# usb_cuter.net
KiCad netlist of a schematic drawn in Altium Designer
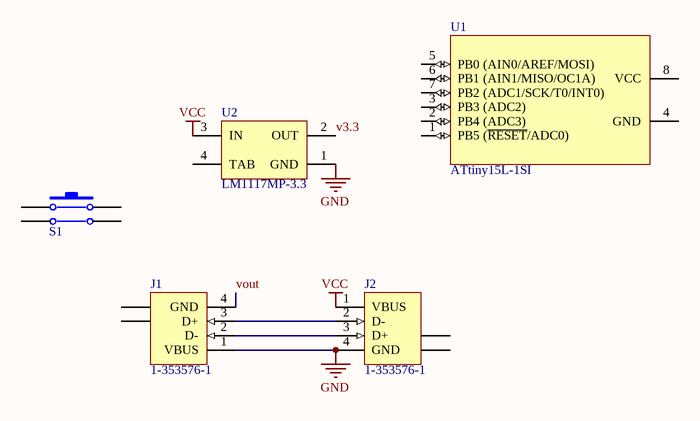
[diagram p0: usb cuter.SchDoc]

(export (version "E")
  (design (tool "Eeschema 10.0.6"))
  (components
    (comp (ref "J1")
      (value "1-353576-1")
      (footprint "353576")
      (description "USB 1.1, Right Angle, SMT, A Type, Receptacle, 4 Position, White")
      (fields (field (name "PUBLISHER") "Altium Limited"))
      (libsource (lib "") (part "1-353576-1_1"))
    )
    (comp (ref "J2")
      (value "1-353576-1")
      (footprint "353576")
      (description "USB 1.1, Right Angle, SMT, A Type, Receptacle, 4 Position, White")
      (fields (field (name "PUBLISHER") "Altium Limited"))
      (libsource (lib "AMP Serial Bus USB") (part "1-353576-1"))
    )
    (comp (ref "S1")
      (value "PUSH BUTTON DOUBLE")
      (footprint "PUSH BUTTON")
      (description "Switch")
      (libsource (lib "AltiumLib1") (part "PUSH BUTTON DOUBLE"))
    )
    (comp (ref "U1")
      (value "ATtiny15L-1SI")
      (footprint "8S2_N")
      (description "8-Bit AVR Microcontroller with 1K Byte of Flash Memory")
      (fields (field (name "PUBLISHER") "Altium Limited"))
      (libsource (lib "Atmel Microcontroller 8-Bit AVR") (part "ATtiny15L-1SI"))
    )
    (comp (ref "U2")
      (value "LM1117MP-3.3")
      (footprint "MP04A_N")
      (description "800mA Low-Dropout Linear Regulator")
      (fields
        (field (name "MANUFACTURER") "National Semiconductor")
        (field (name "DIGIKEYPARTNUMBER") "LM1117MP-3.3CT-ND")
        (field (name "PUBLISHER") "Altium Limited")
      )
      (libsource (lib "NSC LDO") (part "LM1117MP-3.3"))
    )
  )
  (nets
    (net (code "1") (name "/v3.3") (class "Default")
      (node (ref "U2") (pin "2") (pinfunction "OUT_2") (pintype "power_in"))
    )
    (net (code "2") (name "/vout") (class "Default")
      (node (ref "J1") (pin "4") (pinfunction "GND_4") (pintype "power_in"))
    )
    (net (code "3") (name "GND") (class "Default")
      (node (ref "J1") (pin "1") (pinfunction "VBUS_1") (pintype "power_in"))
      (node (ref "J2") (pin "4") (pinfunction "GND_4") (pintype "power_in"))
      (node (ref "U2") (pin "1") (pinfunction "GND_1") (pintype "power_in"))
    )
    (net (code "4") (name "Net-(J1-D+)") (class "Default")
      (node (ref "J1") (pin "3") (pinfunction "D+_3") (pintype "input"))
      (node (ref "J2") (pin "2") (pinfunction "D-_2") (pintype "input"))
    )
    (net (code "5") (name "Net-(J1-D-)") (class "Default")
      (node (ref "J1") (pin "2") (pinfunction "D-_2") (pintype "input"))
      (node (ref "J2") (pin "3") (pinfunction "D+_3") (pintype "input"))
    )
    (net (code "6") (name "VCC") (class "Default")
      (node (ref "J2") (pin "1") (pinfunction "VBUS_1") (pintype "power_in"))
      (node (ref "U2") (pin "3") (pinfunction "IN_3") (pintype "power_in"))
    )
    (net (code "7") (name "unconnected-(J1-SHLD-Pad5)") (class "Default")
      (node (ref "J1") (pin "5") (pinfunction "SHLD_5") (pintype "passive"))
    )
    (net (code "8") (name "unconnected-(J1-SHLD-Pad6)") (class "Default")
      (node (ref "J1") (pin "6") (pinfunction "SHLD_6") (pintype "passive"))
    )
    (net (code "9") (name "unconnected-(J2-SHLD-Pad5)") (class "Default")
      (node (ref "J2") (pin "5") (pinfunction "SHLD_5") (pintype "passive"))
    )
    (net (code "10") (name "unconnected-(J2-SHLD-Pad6)") (class "Default")
      (node (ref "J2") (pin "6") (pinfunction "SHLD_6") (pintype "passive"))
    )
    (net (code "11") (name "unconnected-(S1-Pad1)") (class "Default")
      (node (ref "S1") (pin "1") (pinfunction "1_1") (pintype "passive"))
    )
    (net (code "12") (name "unconnected-(S1-Pad2)") (class "Default")
      (node (ref "S1") (pin "2") (pinfunction "2_2") (pintype "passive"))
    )
    (net (code "13") (name "unconnected-(S1-Pad3)") (class "Default")
      (node (ref "S1") (pin "3") (pinfunction "3_3") (pintype "passive"))
    )
    (net (code "14") (name "unconnected-(S1-Pad4)") (class "Default")
      (node (ref "S1") (pin "4") (pinfunction "4_4") (pintype "passive"))
    )
    (net (code "15") (name "unconnected-(U1-GND-Pad4)") (class "Default")
      (node (ref "U1") (pin "4") (pinfunction "GND_4") (pintype "power_in"))
    )
    (net (code "16") (name "unconnected-(U1-PB0_(AIN0{slash}AREF{slash}MOSI)-Pad5)") (class "Default")
      (node (ref "U1") (pin "5") (pinfunction "PB0_(AIN0/AREF/MOSI)_5") (pintype "bidirectional"))
    )
    (net (code "17") (name "unconnected-(U1-PB1_(AIN1{slash}MISO{slash}OC1A)-Pad6)") (class "Default")
      (node (ref "U1") (pin "6") (pinfunction "PB1_(AIN1/MISO/OC1A)_6") (pintype "bidirectional"))
    )
    (net (code "18") (name "unconnected-(U1-PB2_(ADC1{slash}SCK{slash}T0{slash}INT0)-Pad7)") (class "Default")
      (node (ref "U1") (pin "7") (pinfunction "PB2_(ADC1/SCK/T0/INT0)_7") (pintype "bidirectional"))
    )
    (net (code "19") (name "unconnected-(U1-PB3_(ADC2)-Pad3)") (class "Default")
      (node (ref "U1") (pin "3") (pinfunction "PB3_(ADC2)_3") (pintype "bidirectional"))
    )
    (net (code "20") (name "unconnected-(U1-PB4_(ADC3)-Pad2)") (class "Default")
      (node (ref "U1") (pin "2") (pinfunction "PB4_(ADC3)_2") (pintype "bidirectional"))
    )
    (net (code "21") (name "unconnected-(U1-PB5_(~{RESET}{slash}ADC0)-Pad1)") (class "Default")
      (node (ref "U1") (pin "1") (pinfunction "PB5_(~{RESET}/ADC0)_1") (pintype "bidirectional"))
    )
    (net (code "22") (name "unconnected-(U1-VCC-Pad8)") (class "Default")
      (node (ref "U1") (pin "8") (pinfunction "VCC_8") (pintype "power_in"))
    )
    (net (code "23") (name "unconnected-(U2-TAB-Pad4)") (class "Default")
      (node (ref "U2") (pin "4") (pinfunction "TAB_4") (pintype "power_in"))
    )
  )
)
